# ia.net
KiCad netlist of a schematic drawn in EAGLE
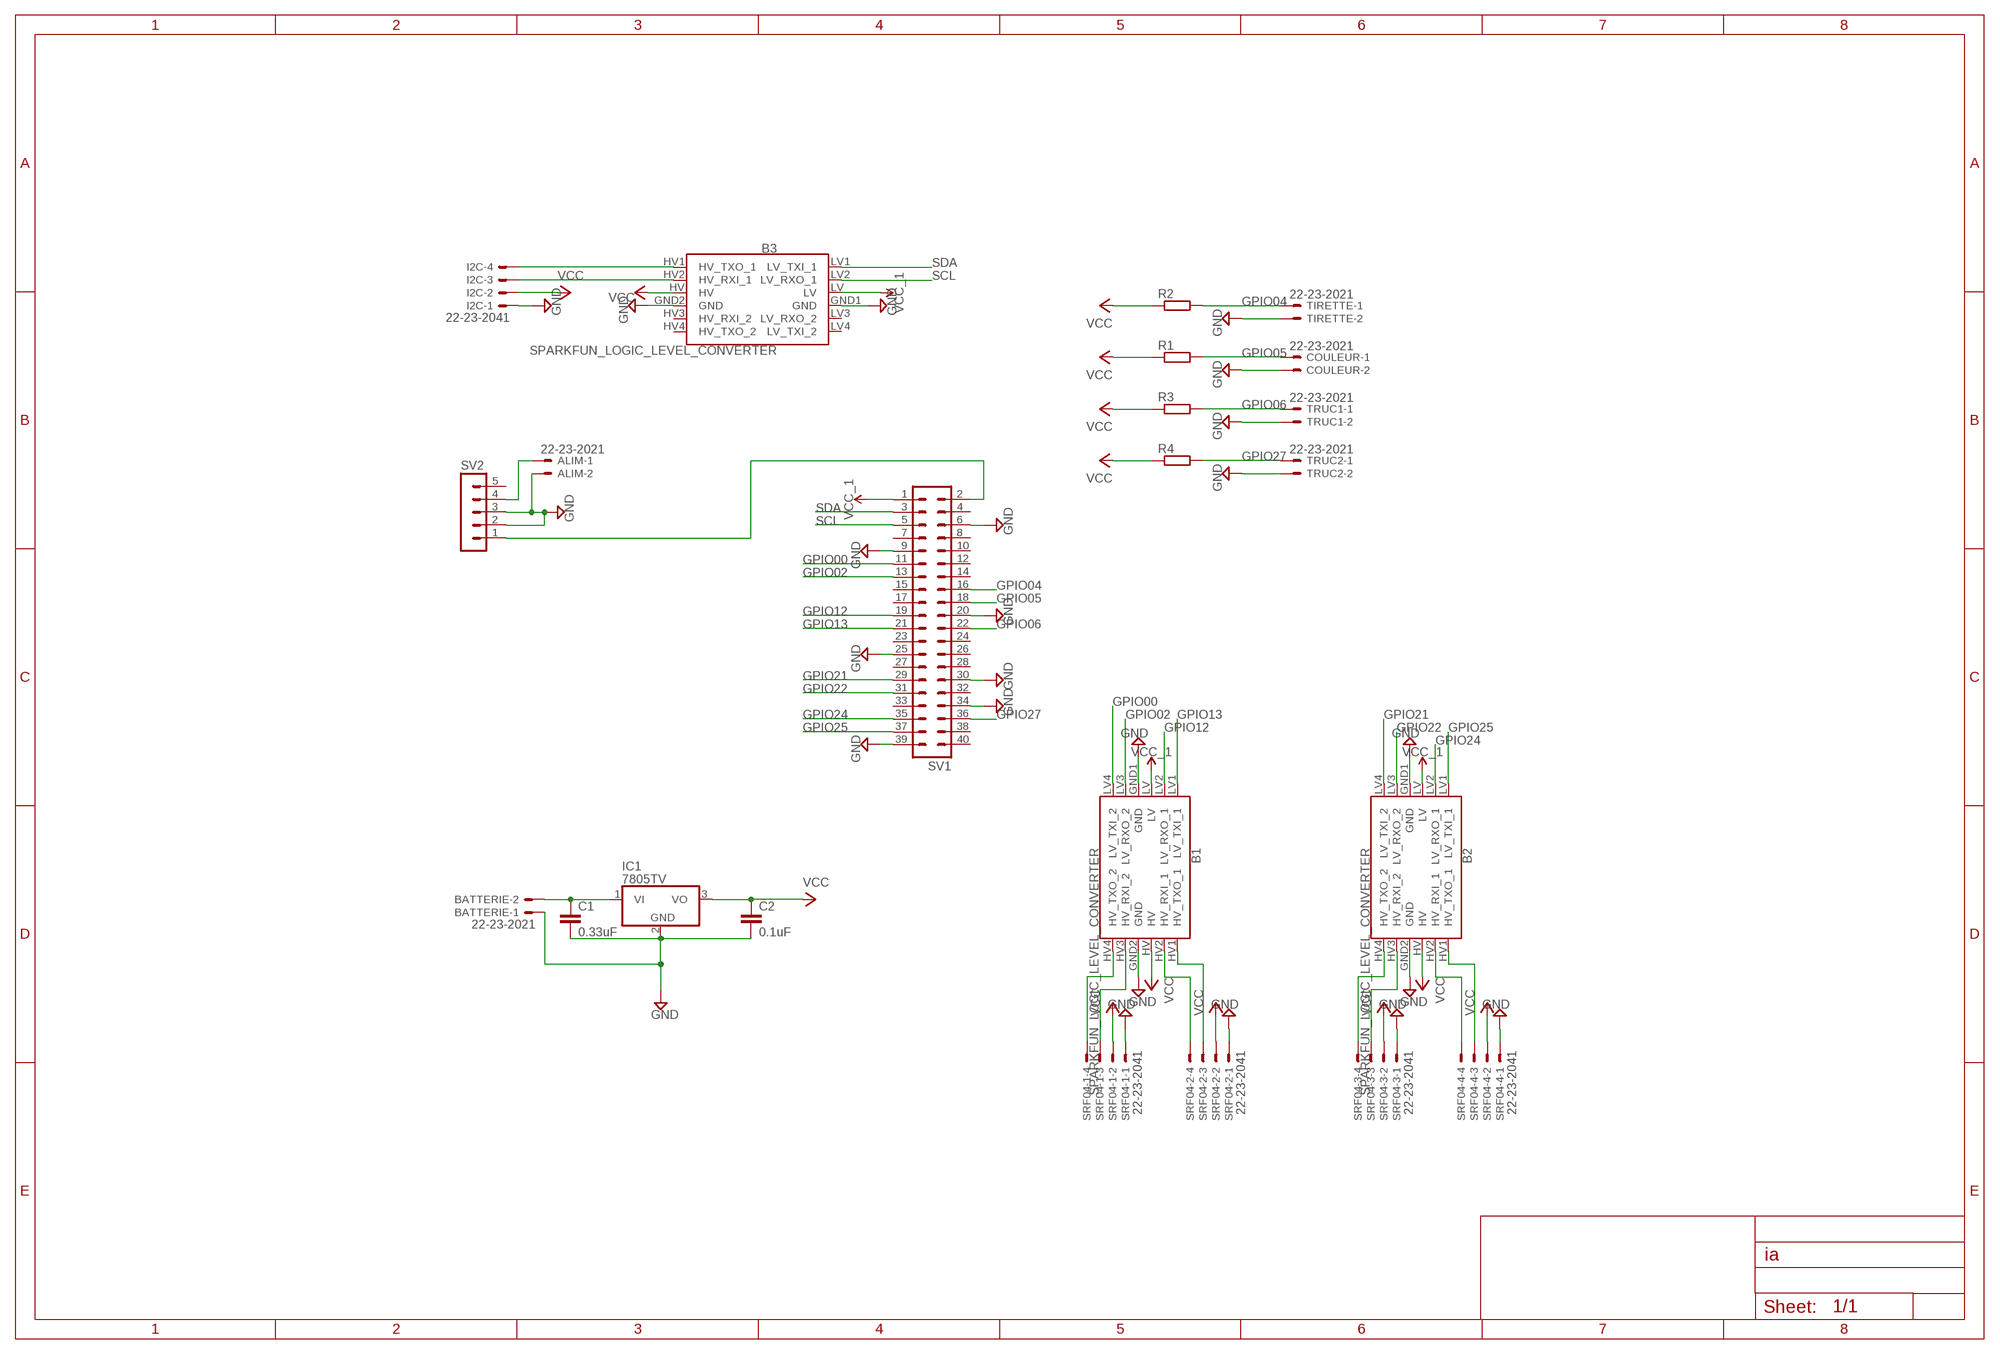
[diagram p0: schematic, sheet 1]

(export (version "E")
  (design (tool "Eeschema 10.0.6"))
  (components
    (comp (ref "ALIM")
      (value "22-23-2021")
      (footprint "eagle-import:22-23-2021")
      (fields (field (name "MF") "MOLEX"))
      (libsource (lib "eagle-import") (part "22-23-2021"))
    )
    (comp (ref "B1")
      (value "SPARKFUN_LOGIC_LEVEL_CONVERTER")
      (footprint "eagle-import:SPARKFUN_LOGIC_LEVEL_CONVERTER")
      (libsource (lib "eagle-import") (part "SPARKFUN_LOGIC_LEVEL_CONVERTER"))
    )
    (comp (ref "B2")
      (value "SPARKFUN_LOGIC_LEVEL_CONVERTER")
      (footprint "eagle-import:SPARKFUN_LOGIC_LEVEL_CONVERTER")
      (libsource (lib "eagle-import") (part "SPARKFUN_LOGIC_LEVEL_CONVERTER"))
    )
    (comp (ref "B3")
      (value "SPARKFUN_LOGIC_LEVEL_CONVERTER")
      (footprint "eagle-import:SPARKFUN_LOGIC_LEVEL_CONVERTER")
      (libsource (lib "eagle-import") (part "SPARKFUN_LOGIC_LEVEL_CONVERTER"))
    )
    (comp (ref "BATTERIE")
      (value "22-23-2021")
      (footprint "eagle-import:22-23-2021")
      (fields (field (name "MF") "MOLEX"))
      (libsource (lib "eagle-import") (part "22-23-2021"))
    )
    (comp (ref "C1")
      (value "0.33uF")
      (footprint "eagle-import:C5B2.5")
      (libsource (lib "eagle-import") (part "C5/2.5"))
    )
    (comp (ref "C2")
      (value "0.1uF")
      (footprint "eagle-import:C5B2.5")
      (libsource (lib "eagle-import") (part "C5/2.5"))
    )
    (comp (ref "COULEUR")
      (value "22-23-2021")
      (footprint "eagle-import:22-23-2021")
      (fields (field (name "MF") "MOLEX"))
      (libsource (lib "eagle-import") (part "22-23-2021"))
    )
    (comp (ref "I2C")
      (value "22-23-2041")
      (footprint "eagle-import:22-23-2041")
      (fields (field (name "MF") "MOLEX"))
      (libsource (lib "eagle-import") (part "22-23-2041"))
    )
    (comp (ref "IC1")
      (value "7805TV")
      (footprint "eagle-import:TO220V")
      (libsource (lib "eagle-import") (part "78TV05"))
    )
    (comp (ref "R1")
      (value "R-EU_0207/15")
      (footprint "eagle-import:0207_15")
      (libsource (lib "eagle-import") (part "R-EU_0207/15"))
    )
    (comp (ref "R2")
      (value "R-EU_0207/15")
      (footprint "eagle-import:0207_15")
      (libsource (lib "eagle-import") (part "R-EU_0207/15"))
    )
    (comp (ref "R3")
      (value "R-EU_0207/15")
      (footprint "eagle-import:0207_15")
      (libsource (lib "eagle-import") (part "R-EU_0207/15"))
    )
    (comp (ref "R4")
      (value "R-EU_0207/15")
      (footprint "eagle-import:0207_15")
      (libsource (lib "eagle-import") (part "R-EU_0207/15"))
    )
    (comp (ref "SRF04-1")
      (value "22-23-2041")
      (footprint "eagle-import:22-23-2041")
      (fields (field (name "MF") "MOLEX"))
      (libsource (lib "eagle-import") (part "22-23-2041"))
    )
    (comp (ref "SRF04-2")
      (value "22-23-2041")
      (footprint "eagle-import:22-23-2041")
      (fields (field (name "MF") "MOLEX"))
      (libsource (lib "eagle-import") (part "22-23-2041"))
    )
    (comp (ref "SRF04-3")
      (value "22-23-2041")
      (footprint "eagle-import:22-23-2041")
      (fields (field (name "MF") "MOLEX"))
      (libsource (lib "eagle-import") (part "22-23-2041"))
    )
    (comp (ref "SRF04-4")
      (value "22-23-2041")
      (footprint "eagle-import:22-23-2041")
      (fields (field (name "MF") "MOLEX"))
      (libsource (lib "eagle-import") (part "22-23-2041"))
    )
    (comp (ref "SV1")
      (value "MA20-2")
      (footprint "eagle-import:MA20-2")
      (libsource (lib "eagle-import") (part "MA20-2"))
    )
    (comp (ref "SV2")
      (value "MA05-1")
      (footprint "eagle-import:MA05-1")
      (libsource (lib "eagle-import") (part "MA05-1"))
    )
    (comp (ref "TIRETTE")
      (value "22-23-2021")
      (footprint "eagle-import:22-23-2021")
      (fields (field (name "MF") "MOLEX"))
      (libsource (lib "eagle-import") (part "22-23-2021"))
    )
    (comp (ref "TRUC1")
      (value "22-23-2021")
      (footprint "eagle-import:22-23-2021")
      (fields (field (name "MF") "MOLEX"))
      (libsource (lib "eagle-import") (part "22-23-2021"))
    )
    (comp (ref "TRUC2")
      (value "22-23-2021")
      (footprint "eagle-import:22-23-2021")
      (fields (field (name "MF") "MOLEX"))
      (libsource (lib "eagle-import") (part "22-23-2021"))
    )
  )
  (nets
    (net (code "1") (name "/GPIO00") (class "Default")
      (node (ref "B1") (pin "LV4") (pinfunction "LV_TXI_2_LV4") (pintype "bidirectional"))
      (node (ref "SV1") (pin "11") (pinfunction "11_11") (pintype "passive"))
    )
    (net (code "2") (name "/GPIO02") (class "Default")
      (node (ref "B1") (pin "LV3") (pinfunction "LV_RXO_2_LV3") (pintype "bidirectional"))
      (node (ref "SV1") (pin "13") (pinfunction "13_13") (pintype "passive"))
    )
    (net (code "3") (name "/GPIO04") (class "Default")
      (node (ref "R2") (pin "2") (pinfunction "2_2") (pintype "passive"))
      (node (ref "SV1") (pin "16") (pinfunction "16_16") (pintype "passive"))
      (node (ref "TIRETTE") (pin "1") (pinfunction "S_1") (pintype "passive"))
    )
    (net (code "4") (name "/GPIO05") (class "Default")
      (node (ref "COULEUR") (pin "1") (pinfunction "S_1") (pintype "passive"))
      (node (ref "R1") (pin "2") (pinfunction "2_2") (pintype "passive"))
      (node (ref "SV1") (pin "18") (pinfunction "18_18") (pintype "passive"))
    )
    (net (code "5") (name "/GPIO06") (class "Default")
      (node (ref "R3") (pin "2") (pinfunction "2_2") (pintype "passive"))
      (node (ref "SV1") (pin "22") (pinfunction "22_22") (pintype "passive"))
      (node (ref "TRUC1") (pin "1") (pinfunction "S_1") (pintype "passive"))
    )
    (net (code "6") (name "/GPIO12") (class "Default")
      (node (ref "B1") (pin "LV2") (pinfunction "LV_RXO_1_LV2") (pintype "bidirectional"))
      (node (ref "SV1") (pin "19") (pinfunction "19_19") (pintype "passive"))
    )
    (net (code "7") (name "/GPIO13") (class "Default")
      (node (ref "B1") (pin "LV1") (pinfunction "LV_TXI_1_LV1") (pintype "bidirectional"))
      (node (ref "SV1") (pin "21") (pinfunction "21_21") (pintype "passive"))
    )
    (net (code "8") (name "/GPIO21") (class "Default")
      (node (ref "B2") (pin "LV4") (pinfunction "LV_TXI_2_LV4") (pintype "bidirectional"))
      (node (ref "SV1") (pin "29") (pinfunction "29_29") (pintype "passive"))
    )
    (net (code "9") (name "/GPIO22") (class "Default")
      (node (ref "B2") (pin "LV3") (pinfunction "LV_RXO_2_LV3") (pintype "bidirectional"))
      (node (ref "SV1") (pin "31") (pinfunction "31_31") (pintype "passive"))
    )
    (net (code "10") (name "/GPIO24") (class "Default")
      (node (ref "B2") (pin "LV2") (pinfunction "LV_RXO_1_LV2") (pintype "bidirectional"))
      (node (ref "SV1") (pin "35") (pinfunction "35_35") (pintype "passive"))
    )
    (net (code "11") (name "/GPIO25") (class "Default")
      (node (ref "B2") (pin "LV1") (pinfunction "LV_TXI_1_LV1") (pintype "bidirectional"))
      (node (ref "SV1") (pin "37") (pinfunction "37_37") (pintype "passive"))
    )
    (net (code "12") (name "/GPIO27") (class "Default")
      (node (ref "R4") (pin "2") (pinfunction "2_2") (pintype "passive"))
      (node (ref "SV1") (pin "36") (pinfunction "36_36") (pintype "passive"))
      (node (ref "TRUC2") (pin "1") (pinfunction "S_1") (pintype "passive"))
    )
    (net (code "13") (name "/SCL") (class "Default")
      (node (ref "B3") (pin "LV2") (pinfunction "LV_RXO_1_LV2") (pintype "bidirectional"))
      (node (ref "SV1") (pin "5") (pinfunction "5_5") (pintype "passive"))
    )
    (net (code "14") (name "/SDA") (class "Default")
      (node (ref "B3") (pin "LV1") (pinfunction "LV_TXI_1_LV1") (pintype "bidirectional"))
      (node (ref "SV1") (pin "3") (pinfunction "3_3") (pintype "passive"))
    )
    (net (code "15") (name "GND") (class "Default")
      (node (ref "ALIM") (pin "2") (pinfunction "S_2") (pintype "passive"))
      (node (ref "B1") (pin "GND1") (pinfunction "GND_GND1") (pintype "power_in"))
      (node (ref "B1") (pin "GND2") (pinfunction "GND_GND2") (pintype "power_in"))
      (node (ref "B2") (pin "GND1") (pinfunction "GND_GND1") (pintype "power_in"))
      (node (ref "B2") (pin "GND2") (pinfunction "GND_GND2") (pintype "power_in"))
      (node (ref "B3") (pin "GND1") (pinfunction "GND_GND1") (pintype "power_in"))
      (node (ref "B3") (pin "GND2") (pinfunction "GND_GND2") (pintype "power_in"))
      (node (ref "BATTERIE") (pin "1") (pinfunction "S_1") (pintype "passive"))
      (node (ref "C1") (pin "2") (pinfunction "2_2") (pintype "passive"))
      (node (ref "C2") (pin "2") (pinfunction "2_2") (pintype "passive"))
      (node (ref "COULEUR") (pin "2") (pinfunction "S_2") (pintype "passive"))
      (node (ref "I2C") (pin "1") (pinfunction "S_1") (pintype "passive"))
      (node (ref "IC1") (pin "2") (pinfunction "GND_2") (pintype "passive"))
      (node (ref "SRF04-1") (pin "1") (pinfunction "S_1") (pintype "passive"))
      (node (ref "SRF04-2") (pin "1") (pinfunction "S_1") (pintype "passive"))
      (node (ref "SRF04-3") (pin "1") (pinfunction "S_1") (pintype "passive"))
      (node (ref "SRF04-4") (pin "1") (pinfunction "S_1") (pintype "passive"))
      (node (ref "SV1") (pin "20") (pinfunction "20_20") (pintype "passive"))
      (node (ref "SV1") (pin "25") (pinfunction "25_25") (pintype "passive"))
      (node (ref "SV1") (pin "30") (pinfunction "30_30") (pintype "passive"))
      (node (ref "SV1") (pin "34") (pinfunction "34_34") (pintype "passive"))
      (node (ref "SV1") (pin "39") (pinfunction "39_39") (pintype "passive"))
      (node (ref "SV1") (pin "6") (pinfunction "6_6") (pintype "passive"))
      (node (ref "SV1") (pin "9") (pinfunction "9_9") (pintype "passive"))
      (node (ref "SV2") (pin "2") (pinfunction "2_2") (pintype "passive"))
      (node (ref "SV2") (pin "3") (pinfunction "3_3") (pintype "passive"))
      (node (ref "TIRETTE") (pin "2") (pinfunction "S_2") (pintype "passive"))
      (node (ref "TRUC1") (pin "2") (pinfunction "S_2") (pintype "passive"))
      (node (ref "TRUC2") (pin "2") (pinfunction "S_2") (pintype "passive"))
    )
    (net (code "16") (name "Net-(ALIMA-S)") (class "Default")
      (node (ref "ALIM") (pin "1") (pinfunction "S_1") (pintype "passive"))
      (node (ref "SV2") (pin "4") (pinfunction "4_4") (pintype "passive"))
    )
    (net (code "17") (name "Net-(B1-HV_RXI_1)") (class "Default")
      (node (ref "B1") (pin "HV2") (pinfunction "HV_RXI_1_HV2") (pintype "bidirectional"))
      (node (ref "SRF04-2") (pin "4") (pinfunction "S_4") (pintype "passive"))
    )
    (net (code "18") (name "Net-(B1-HV_RXI_2)") (class "Default")
      (node (ref "B1") (pin "HV3") (pinfunction "HV_RXI_2_HV3") (pintype "bidirectional"))
      (node (ref "SRF04-1") (pin "3") (pinfunction "S_3") (pintype "passive"))
    )
    (net (code "19") (name "Net-(B1-HV_TXO_1)") (class "Default")
      (node (ref "B1") (pin "HV1") (pinfunction "HV_TXO_1_HV1") (pintype "bidirectional"))
      (node (ref "SRF04-2") (pin "3") (pinfunction "S_3") (pintype "passive"))
    )
    (net (code "20") (name "Net-(B1-HV_TXO_2)") (class "Default")
      (node (ref "B1") (pin "HV4") (pinfunction "HV_TXO_2_HV4") (pintype "bidirectional"))
      (node (ref "SRF04-1") (pin "4") (pinfunction "S_4") (pintype "passive"))
    )
    (net (code "21") (name "Net-(B2-HV_RXI_1)") (class "Default")
      (node (ref "B2") (pin "HV2") (pinfunction "HV_RXI_1_HV2") (pintype "bidirectional"))
      (node (ref "SRF04-4") (pin "4") (pinfunction "S_4") (pintype "passive"))
    )
    (net (code "22") (name "Net-(B2-HV_RXI_2)") (class "Default")
      (node (ref "B2") (pin "HV3") (pinfunction "HV_RXI_2_HV3") (pintype "bidirectional"))
      (node (ref "SRF04-3") (pin "3") (pinfunction "S_3") (pintype "passive"))
    )
    (net (code "23") (name "Net-(B2-HV_TXO_1)") (class "Default")
      (node (ref "B2") (pin "HV1") (pinfunction "HV_TXO_1_HV1") (pintype "bidirectional"))
      (node (ref "SRF04-4") (pin "3") (pinfunction "S_3") (pintype "passive"))
    )
    (net (code "24") (name "Net-(B2-HV_TXO_2)") (class "Default")
      (node (ref "B2") (pin "HV4") (pinfunction "HV_TXO_2_HV4") (pintype "bidirectional"))
      (node (ref "SRF04-3") (pin "4") (pinfunction "S_4") (pintype "passive"))
    )
    (net (code "25") (name "Net-(B3-HV_RXI_1)") (class "Default")
      (node (ref "B3") (pin "HV2") (pinfunction "HV_RXI_1_HV2") (pintype "bidirectional"))
      (node (ref "I2C") (pin "3") (pinfunction "S_3") (pintype "passive"))
    )
    (net (code "26") (name "Net-(B3-HV_TXO_1)") (class "Default")
      (node (ref "B3") (pin "HV1") (pinfunction "HV_TXO_1_HV1") (pintype "bidirectional"))
      (node (ref "I2C") (pin "4") (pinfunction "S_4") (pintype "passive"))
    )
    (net (code "27") (name "Net-(BATTERIEB-S)") (class "Default")
      (node (ref "BATTERIE") (pin "2") (pinfunction "S_2") (pintype "passive"))
      (node (ref "C1") (pin "1") (pinfunction "1_1") (pintype "passive"))
      (node (ref "IC1") (pin "1") (pinfunction "VI_1") (pintype "input"))
    )
    (net (code "28") (name "Net-(SV1-Pad2)") (class "Default")
      (node (ref "SV1") (pin "2") (pinfunction "2_2") (pintype "passive"))
      (node (ref "SV2") (pin "1") (pinfunction "1_1") (pintype "passive"))
    )
    (net (code "29") (name "VCC") (class "Default")
      (node (ref "B1") (pin "HV") (pinfunction "HV_HV") (pintype "power_in"))
      (node (ref "B2") (pin "HV") (pinfunction "HV_HV") (pintype "power_in"))
      (node (ref "B3") (pin "HV") (pinfunction "HV_HV") (pintype "power_in"))
      (node (ref "C2") (pin "1") (pinfunction "1_1") (pintype "passive"))
      (node (ref "I2C") (pin "2") (pinfunction "S_2") (pintype "passive"))
      (node (ref "IC1") (pin "3") (pinfunction "VO_3") (pintype "passive"))
      (node (ref "R1") (pin "1") (pinfunction "1_1") (pintype "passive"))
      (node (ref "R2") (pin "1") (pinfunction "1_1") (pintype "passive"))
      (node (ref "R3") (pin "1") (pinfunction "1_1") (pintype "passive"))
      (node (ref "R4") (pin "1") (pinfunction "1_1") (pintype "passive"))
      (node (ref "SRF04-1") (pin "2") (pinfunction "S_2") (pintype "passive"))
      (node (ref "SRF04-2") (pin "2") (pinfunction "S_2") (pintype "passive"))
      (node (ref "SRF04-3") (pin "2") (pinfunction "S_2") (pintype "passive"))
      (node (ref "SRF04-4") (pin "2") (pinfunction "S_2") (pintype "passive"))
    )
    (net (code "30") (name "VCC_1") (class "Default")
      (node (ref "B1") (pin "LV") (pinfunction "LV_LV") (pintype "power_in"))
      (node (ref "B2") (pin "LV") (pinfunction "LV_LV") (pintype "power_in"))
      (node (ref "B3") (pin "LV") (pinfunction "LV_LV") (pintype "power_in"))
      (node (ref "SV1") (pin "1") (pinfunction "1_1") (pintype "passive"))
    )
    (net (code "31") (name "unconnected-(B3-HV_RXI_2-PadHV3)") (class "Default")
      (node (ref "B3") (pin "HV3") (pinfunction "HV_RXI_2_HV3") (pintype "bidirectional"))
    )
    (net (code "32") (name "unconnected-(B3-HV_TXO_2-PadHV4)") (class "Default")
      (node (ref "B3") (pin "HV4") (pinfunction "HV_TXO_2_HV4") (pintype "bidirectional"))
    )
    (net (code "33") (name "unconnected-(B3-LV_RXO_2-PadLV3)") (class "Default")
      (node (ref "B3") (pin "LV3") (pinfunction "LV_RXO_2_LV3") (pintype "bidirectional"))
    )
    (net (code "34") (name "unconnected-(B3-LV_TXI_2-PadLV4)") (class "Default")
      (node (ref "B3") (pin "LV4") (pinfunction "LV_TXI_2_LV4") (pintype "bidirectional"))
    )
    (net (code "35") (name "unconnected-(SV1-Pad4)") (class "Default")
      (node (ref "SV1") (pin "4") (pinfunction "4_4") (pintype "passive"))
    )
    (net (code "36") (name "unconnected-(SV1-Pad7)") (class "Default")
      (node (ref "SV1") (pin "7") (pinfunction "7_7") (pintype "passive"))
    )
    (net (code "37") (name "unconnected-(SV1-Pad8)") (class "Default")
      (node (ref "SV1") (pin "8") (pinfunction "8_8") (pintype "passive"))
    )
    (net (code "38") (name "unconnected-(SV1-Pad10)") (class "Default")
      (node (ref "SV1") (pin "10") (pinfunction "10_10") (pintype "passive"))
    )
    (net (code "39") (name "unconnected-(SV1-Pad12)") (class "Default")
      (node (ref "SV1") (pin "12") (pinfunction "12_12") (pintype "passive"))
    )
    (net (code "40") (name "unconnected-(SV1-Pad14)") (class "Default")
      (node (ref "SV1") (pin "14") (pinfunction "14_14") (pintype "passive"))
    )
    (net (code "41") (name "unconnected-(SV1-Pad15)") (class "Default")
      (node (ref "SV1") (pin "15") (pinfunction "15_15") (pintype "passive"))
    )
    (net (code "42") (name "unconnected-(SV1-Pad17)") (class "Default")
      (node (ref "SV1") (pin "17") (pinfunction "17_17") (pintype "passive"))
    )
    (net (code "43") (name "unconnected-(SV1-Pad23)") (class "Default")
      (node (ref "SV1") (pin "23") (pinfunction "23_23") (pintype "passive"))
    )
    (net (code "44") (name "unconnected-(SV1-Pad24)") (class "Default")
      (node (ref "SV1") (pin "24") (pinfunction "24_24") (pintype "passive"))
    )
    (net (code "45") (name "unconnected-(SV1-Pad26)") (class "Default")
      (node (ref "SV1") (pin "26") (pinfunction "26_26") (pintype "passive"))
    )
    (net (code "46") (name "unconnected-(SV1-Pad27)") (class "Default")
      (node (ref "SV1") (pin "27") (pinfunction "27_27") (pintype "passive"))
    )
    (net (code "47") (name "unconnected-(SV1-Pad28)") (class "Default")
      (node (ref "SV1") (pin "28") (pinfunction "28_28") (pintype "passive"))
    )
    (net (code "48") (name "unconnected-(SV1-Pad32)") (class "Default")
      (node (ref "SV1") (pin "32") (pinfunction "32_32") (pintype "passive"))
    )
    (net (code "49") (name "unconnected-(SV1-Pad33)") (class "Default")
      (node (ref "SV1") (pin "33") (pinfunction "33_33") (pintype "passive"))
    )
    (net (code "50") (name "unconnected-(SV1-Pad38)") (class "Default")
      (node (ref "SV1") (pin "38") (pinfunction "38_38") (pintype "passive"))
    )
    (net (code "51") (name "unconnected-(SV1-Pad40)") (class "Default")
      (node (ref "SV1") (pin "40") (pinfunction "40_40") (pintype "passive"))
    )
    (net (code "52") (name "unconnected-(SV2-Pad5)") (class "Default")
      (node (ref "SV2") (pin "5") (pinfunction "5_5") (pintype "passive"))
    )
  )
)
